# PlacaE3.net
KiCad netlist of a schematic drawn in Altium Designer
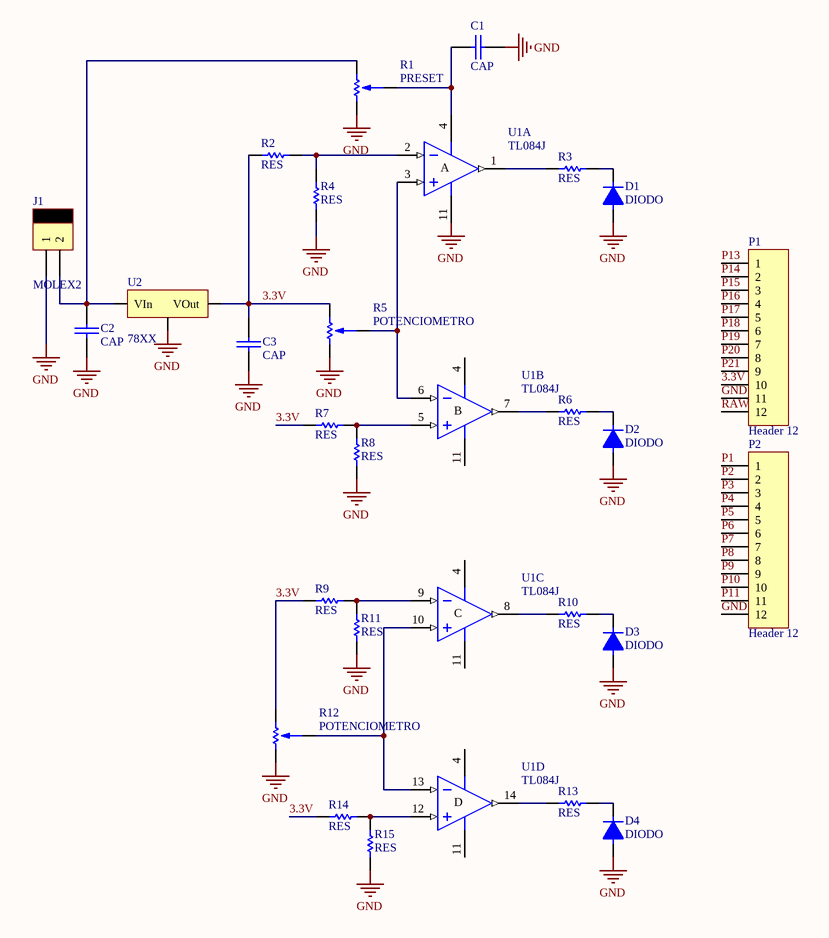
[diagram p0: PlacaE3.SchDoc]

(export (version "E")
  (design (tool "Eeschema 10.0.6"))
  (components
    (comp (ref "C1") (value "CAP") (footprint "CAP200") (libsource (lib "LIBEBAL") (part "CAP")))
    (comp (ref "C2") (value "CAP") (footprint "CAP200") (libsource (lib "LIBEBAL") (part "CAP")))
    (comp (ref "C3") (value "CAP") (footprint "CAP200") (libsource (lib "LIBEBAL") (part "CAP")))
    (comp (ref "D1") (value "DIODO") (footprint "DO41") (libsource (lib "LIBEBAL") (part "DIODO")))
    (comp (ref "D2") (value "DIODO") (footprint "DO41") (libsource (lib "LIBEBAL") (part "DIODO")))
    (comp (ref "D3") (value "DIODO") (footprint "DO41") (libsource (lib "LIBEBAL") (part "DIODO")))
    (comp (ref "D4") (value "DIODO") (footprint "DO41") (libsource (lib "LIBEBAL") (part "DIODO")))
    (comp (ref "J1") (value "MOLEX2") (footprint "MOLEX2") (libsource (lib "LIBEBAL") (part "MOLEX2")))
    (comp (ref "P1")
      (value "Header 12")
      (footprint "HDR1X12")
      (description "Header, 12-Pin")
      (fields (field (name "PUBLISHER") "Altium Limited"))
      (libsource (lib "Miscellaneous Connectors") (part "Header 12"))
    )
    (comp (ref "P2")
      (value "Header 12")
      (footprint "HDR1X12")
      (description "Header, 12-Pin")
      (fields (field (name "PUBLISHER") "Altium Limited"))
      (libsource (lib "Miscellaneous Connectors") (part "Header 12"))
    )
    (comp (ref "R1") (value "PRESET") (footprint "PRESET V") (libsource (lib "LIBEBAL") (part "PRESET")))
    (comp (ref "R2") (value "RES") (footprint "RES400") (libsource (lib "LIBEBAL") (part "RES")))
    (comp (ref "R3") (value "RES") (footprint "RES400") (libsource (lib "LIBEBAL") (part "RES")))
    (comp (ref "R4") (value "RES") (footprint "RES400") (libsource (lib "LIBEBAL") (part "RES")))
    (comp (ref "R5")
      (value "POTENCIOMETRO")
      (footprint "POTENCIOMETRO")
      (libsource (lib "LIBEBAL") (part "POTENCIOMETRO"))
    )
    (comp (ref "R6") (value "RES") (footprint "RES400") (libsource (lib "LIBEBAL") (part "RES")))
    (comp (ref "R7") (value "RES") (footprint "RES400") (libsource (lib "LIBEBAL") (part "RES")))
    (comp (ref "R8") (value "RES") (footprint "RES400") (libsource (lib "LIBEBAL") (part "RES")))
    (comp (ref "R9") (value "RES") (footprint "RES400") (libsource (lib "LIBEBAL") (part "RES")))
    (comp (ref "R10") (value "RES") (footprint "RES400") (libsource (lib "LIBEBAL") (part "RES")))
    (comp (ref "R11") (value "RES") (footprint "RES400") (libsource (lib "LIBEBAL") (part "RES")))
    (comp (ref "R12")
      (value "POTENCIOMETRO")
      (footprint "POTENCIOMETRO")
      (libsource (lib "LIBEBAL") (part "POTENCIOMETRO"))
    )
    (comp (ref "R13") (value "RES") (footprint "RES400") (libsource (lib "LIBEBAL") (part "RES")))
    (comp (ref "R14") (value "RES") (footprint "RES400") (libsource (lib "LIBEBAL") (part "RES")))
    (comp (ref "R15") (value "RES") (footprint "RES400") (libsource (lib "LIBEBAL") (part "RES")))
    (comp (ref "U1")
      (value "TL084J")
      (footprint "J014")
      (description "JFET-Input Operational Amplifier")
      (fields (field (name "PUBLISHER") "Altium Limited"))
      (libsource (lib "TI Operational Amplifier") (part "TL084J"))
    )
    (comp (ref "U2")
      (value "78XX")
      (footprint "TO-220 V")
      (description "REGULDOR POSITIVO")
      (libsource (lib "LIBEBAL") (part "78XX"))
    )
  )
  (nets
    (net (code "1") (name "/3.3V") (class "Default")
      (node (ref "C3") (pin "1") (pinfunction "1_1") (pintype "passive"))
      (node (ref "P1") (pin "10") (pinfunction "10_10") (pintype "passive"))
      (node (ref "R12") (pin "1") (pinfunction "1_1") (pintype "passive"))
      (node (ref "R14") (pin "1") (pinfunction "1_1") (pintype "passive"))
      (node (ref "R2") (pin "1") (pinfunction "1_1") (pintype "passive"))
      (node (ref "R5") (pin "1") (pinfunction "1_1") (pintype "passive"))
      (node (ref "R7") (pin "1") (pinfunction "1_1") (pintype "passive"))
      (node (ref "R9") (pin "1") (pinfunction "1_1") (pintype "passive"))
      (node (ref "U2") (pin "3") (pinfunction "VOut_3") (pintype "passive"))
    )
    (net (code "2") (name "/P1") (class "Default")
      (node (ref "P2") (pin "1") (pinfunction "1_1") (pintype "passive"))
    )
    (net (code "3") (name "/P2") (class "Default")
      (node (ref "P2") (pin "2") (pinfunction "2_2") (pintype "passive"))
    )
    (net (code "4") (name "/P3") (class "Default")
      (node (ref "P2") (pin "3") (pinfunction "3_3") (pintype "passive"))
    )
    (net (code "5") (name "/P4") (class "Default")
      (node (ref "P2") (pin "4") (pinfunction "4_4") (pintype "passive"))
    )
    (net (code "6") (name "/P5") (class "Default")
      (node (ref "P2") (pin "5") (pinfunction "5_5") (pintype "passive"))
    )
    (net (code "7") (name "/P6") (class "Default")
      (node (ref "P2") (pin "6") (pinfunction "6_6") (pintype "passive"))
    )
    (net (code "8") (name "/P7") (class "Default")
      (node (ref "P2") (pin "7") (pinfunction "7_7") (pintype "passive"))
    )
    (net (code "9") (name "/P8") (class "Default")
      (node (ref "P2") (pin "8") (pinfunction "8_8") (pintype "passive"))
    )
    (net (code "10") (name "/P9") (class "Default")
      (node (ref "P2") (pin "9") (pinfunction "9_9") (pintype "passive"))
    )
    (net (code "11") (name "/P10") (class "Default")
      (node (ref "P2") (pin "10") (pinfunction "10_10") (pintype "passive"))
    )
    (net (code "12") (name "/P11") (class "Default")
      (node (ref "P2") (pin "11") (pinfunction "11_11") (pintype "passive"))
    )
    (net (code "13") (name "/P13") (class "Default")
      (node (ref "P1") (pin "1") (pinfunction "1_1") (pintype "passive"))
    )
    (net (code "14") (name "/P14") (class "Default")
      (node (ref "P1") (pin "2") (pinfunction "2_2") (pintype "passive"))
    )
    (net (code "15") (name "/P15") (class "Default")
      (node (ref "P1") (pin "3") (pinfunction "3_3") (pintype "passive"))
    )
    (net (code "16") (name "/P16") (class "Default")
      (node (ref "P1") (pin "4") (pinfunction "4_4") (pintype "passive"))
    )
    (net (code "17") (name "/P17") (class "Default")
      (node (ref "P1") (pin "5") (pinfunction "5_5") (pintype "passive"))
    )
    (net (code "18") (name "/P18") (class "Default")
      (node (ref "P1") (pin "6") (pinfunction "6_6") (pintype "passive"))
    )
    (net (code "19") (name "/P19") (class "Default")
      (node (ref "P1") (pin "7") (pinfunction "7_7") (pintype "passive"))
    )
    (net (code "20") (name "/P20") (class "Default")
      (node (ref "P1") (pin "8") (pinfunction "8_8") (pintype "passive"))
    )
    (net (code "21") (name "/P21") (class "Default")
      (node (ref "P1") (pin "9") (pinfunction "9_9") (pintype "passive"))
    )
    (net (code "22") (name "/RAW") (class "Default")
      (node (ref "P1") (pin "12") (pinfunction "12_12") (pintype "passive"))
    )
    (net (code "23") (name "GND") (class "Default")
      (node (ref "C1") (pin "2") (pinfunction "2_2") (pintype "passive"))
      (node (ref "C2") (pin "2") (pinfunction "2_2") (pintype "passive"))
      (node (ref "C3") (pin "2") (pinfunction "2_2") (pintype "passive"))
      (node (ref "D1") (pin "1") (pinfunction "1_1") (pintype "passive"))
      (node (ref "D2") (pin "1") (pinfunction "1_1") (pintype "passive"))
      (node (ref "D3") (pin "1") (pinfunction "1_1") (pintype "passive"))
      (node (ref "D4") (pin "1") (pinfunction "1_1") (pintype "passive"))
      (node (ref "J1") (pin "1") (pinfunction "1_1") (pintype "passive"))
      (node (ref "P1") (pin "11") (pinfunction "11_11") (pintype "passive"))
      (node (ref "P2") (pin "12") (pinfunction "12_12") (pintype "passive"))
      (node (ref "R1") (pin "3") (pinfunction "3_3") (pintype "passive"))
      (node (ref "R11") (pin "1") (pinfunction "1_1") (pintype "passive"))
      (node (ref "R12") (pin "3") (pinfunction "3_3") (pintype "passive"))
      (node (ref "R15") (pin "1") (pinfunction "1_1") (pintype "passive"))
      (node (ref "R4") (pin "1") (pinfunction "1_1") (pintype "passive"))
      (node (ref "R5") (pin "3") (pinfunction "3_3") (pintype "passive"))
      (node (ref "R8") (pin "1") (pinfunction "1_1") (pintype "passive"))
      (node (ref "U1") (pin "11") (pinfunction "V-_11") (pintype "power_in"))
      (node (ref "U2") (pin "2") (pinfunction "GND_2") (pintype "passive"))
    )
    (net (code "24") (name "Net-(D1-Pad2)") (class "Default")
      (node (ref "D1") (pin "2") (pinfunction "2_2") (pintype "passive"))
      (node (ref "R3") (pin "2") (pinfunction "2_2") (pintype "passive"))
    )
    (net (code "25") (name "Net-(D2-Pad2)") (class "Default")
      (node (ref "D2") (pin "2") (pinfunction "2_2") (pintype "passive"))
      (node (ref "R6") (pin "2") (pinfunction "2_2") (pintype "passive"))
    )
    (net (code "26") (name "Net-(D3-Pad2)") (class "Default")
      (node (ref "D3") (pin "2") (pinfunction "2_2") (pintype "passive"))
      (node (ref "R10") (pin "2") (pinfunction "2_2") (pintype "passive"))
    )
    (net (code "27") (name "Net-(D4-Pad2)") (class "Default")
      (node (ref "D4") (pin "2") (pinfunction "2_2") (pintype "passive"))
      (node (ref "R13") (pin "2") (pinfunction "2_2") (pintype "passive"))
    )
    (net (code "28") (name "Net-(U1A-IN+)") (class "Default")
      (node (ref "R5") (pin "2") (pinfunction "2_2") (pintype "passive"))
      (node (ref "U1") (pin "3") (pinfunction "IN+_3") (pintype "input"))
      (node (ref "U1") (pin "6") (pinfunction "IN-_6") (pintype "input"))
    )
    (net (code "29") (name "Net-(U1A-IN-)") (class "Default")
      (node (ref "R2") (pin "2") (pinfunction "2_2") (pintype "passive"))
      (node (ref "R4") (pin "2") (pinfunction "2_2") (pintype "passive"))
      (node (ref "U1") (pin "2") (pinfunction "IN-_2") (pintype "input"))
    )
    (net (code "30") (name "Net-(U1A-OUT)") (class "Default")
      (node (ref "R3") (pin "1") (pinfunction "1_1") (pintype "passive"))
      (node (ref "U1") (pin "1") (pinfunction "OUT_1") (pintype "output"))
    )
    (net (code "31") (name "Net-(U1A-V+)") (class "Default")
      (node (ref "C1") (pin "1") (pinfunction "1_1") (pintype "passive"))
      (node (ref "R1") (pin "2") (pinfunction "2_2") (pintype "passive"))
      (node (ref "U1") (pin "4") (pinfunction "V+_4") (pintype "power_in"))
    )
    (net (code "32") (name "Net-(U1B-IN+)") (class "Default")
      (node (ref "R7") (pin "2") (pinfunction "2_2") (pintype "passive"))
      (node (ref "R8") (pin "2") (pinfunction "2_2") (pintype "passive"))
      (node (ref "U1") (pin "5") (pinfunction "IN+_5") (pintype "input"))
    )
    (net (code "33") (name "Net-(U1B-OUT)") (class "Default")
      (node (ref "R6") (pin "1") (pinfunction "1_1") (pintype "passive"))
      (node (ref "U1") (pin "7") (pinfunction "OUT_7") (pintype "output"))
    )
    (net (code "34") (name "Net-(U1C-IN+)") (class "Default")
      (node (ref "R12") (pin "2") (pinfunction "2_2") (pintype "passive"))
      (node (ref "U1") (pin "10") (pinfunction "IN+_10") (pintype "input"))
      (node (ref "U1") (pin "13") (pinfunction "IN-_13") (pintype "input"))
    )
    (net (code "35") (name "Net-(U1C-IN-)") (class "Default")
      (node (ref "R11") (pin "2") (pinfunction "2_2") (pintype "passive"))
      (node (ref "R9") (pin "2") (pinfunction "2_2") (pintype "passive"))
      (node (ref "U1") (pin "9") (pinfunction "IN-_9") (pintype "input"))
    )
    (net (code "36") (name "Net-(U1C-OUT)") (class "Default")
      (node (ref "R10") (pin "1") (pinfunction "1_1") (pintype "passive"))
      (node (ref "U1") (pin "8") (pinfunction "OUT_8") (pintype "output"))
    )
    (net (code "37") (name "Net-(U1D-IN+)") (class "Default")
      (node (ref "R14") (pin "2") (pinfunction "2_2") (pintype "passive"))
      (node (ref "R15") (pin "2") (pinfunction "2_2") (pintype "passive"))
      (node (ref "U1") (pin "12") (pinfunction "IN+_12") (pintype "input"))
    )
    (net (code "38") (name "Net-(U1D-OUT)") (class "Default")
      (node (ref "R13") (pin "1") (pinfunction "1_1") (pintype "passive"))
      (node (ref "U1") (pin "14") (pinfunction "OUT_14") (pintype "output"))
    )
    (net (code "39") (name "Net-(U2-VIn)") (class "Default")
      (node (ref "C2") (pin "1") (pinfunction "1_1") (pintype "passive"))
      (node (ref "J1") (pin "2") (pinfunction "2_2") (pintype "passive"))
      (node (ref "R1") (pin "1") (pinfunction "1_1") (pintype "passive"))
      (node (ref "U2") (pin "1") (pinfunction "VIn_1") (pintype "passive"))
    )
    (net (code "40") (name "unconnected-(U1B-V+-Pad4)") (class "Default")
      (node (ref "U1") (pin "4") (pinfunction "V+_4") (pintype "power_in"))
    )
    (net (code "41") (name "unconnected-(U1B-V--Pad11)") (class "Default")
      (node (ref "U1") (pin "11") (pinfunction "V-_11") (pintype "power_in"))
    )
    (net (code "42") (name "unconnected-(U1C-V+-Pad4)") (class "Default")
      (node (ref "U1") (pin "4") (pinfunction "V+_4") (pintype "power_in"))
    )
    (net (code "43") (name "unconnected-(U1C-V--Pad11)") (class "Default")
      (node (ref "U1") (pin "11") (pinfunction "V-_11") (pintype "power_in"))
    )
    (net (code "44") (name "unconnected-(U1D-V+-Pad4)") (class "Default")
      (node (ref "U1") (pin "4") (pinfunction "V+_4") (pintype "power_in"))
    )
    (net (code "45") (name "unconnected-(U1D-V--Pad11)") (class "Default")
      (node (ref "U1") (pin "11") (pinfunction "V-_11") (pintype "power_in"))
    )
  )
)
